# AQS.net
KiCad netlist of a schematic drawn in EAGLE
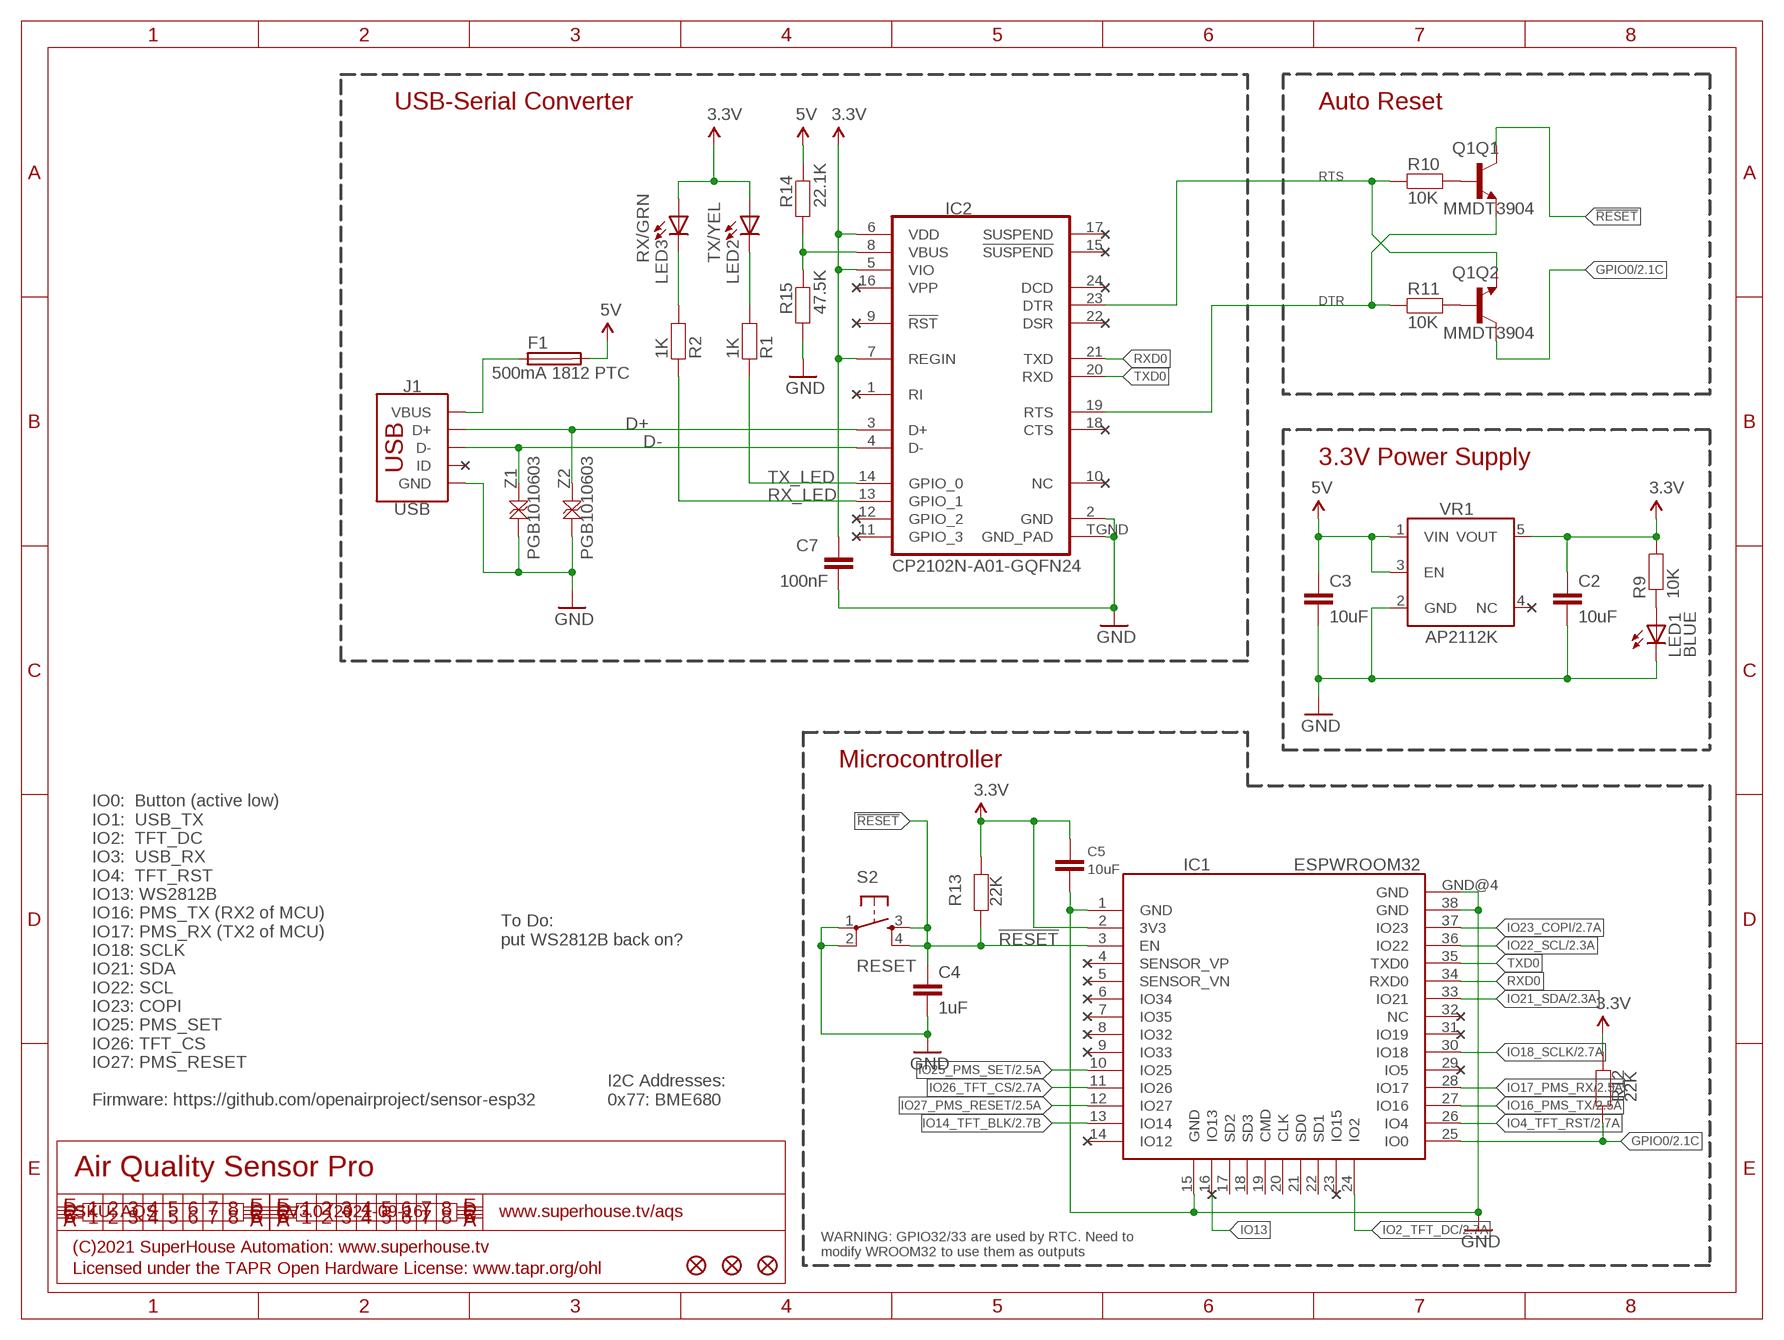
[diagram p0: schematic, sheet 1]
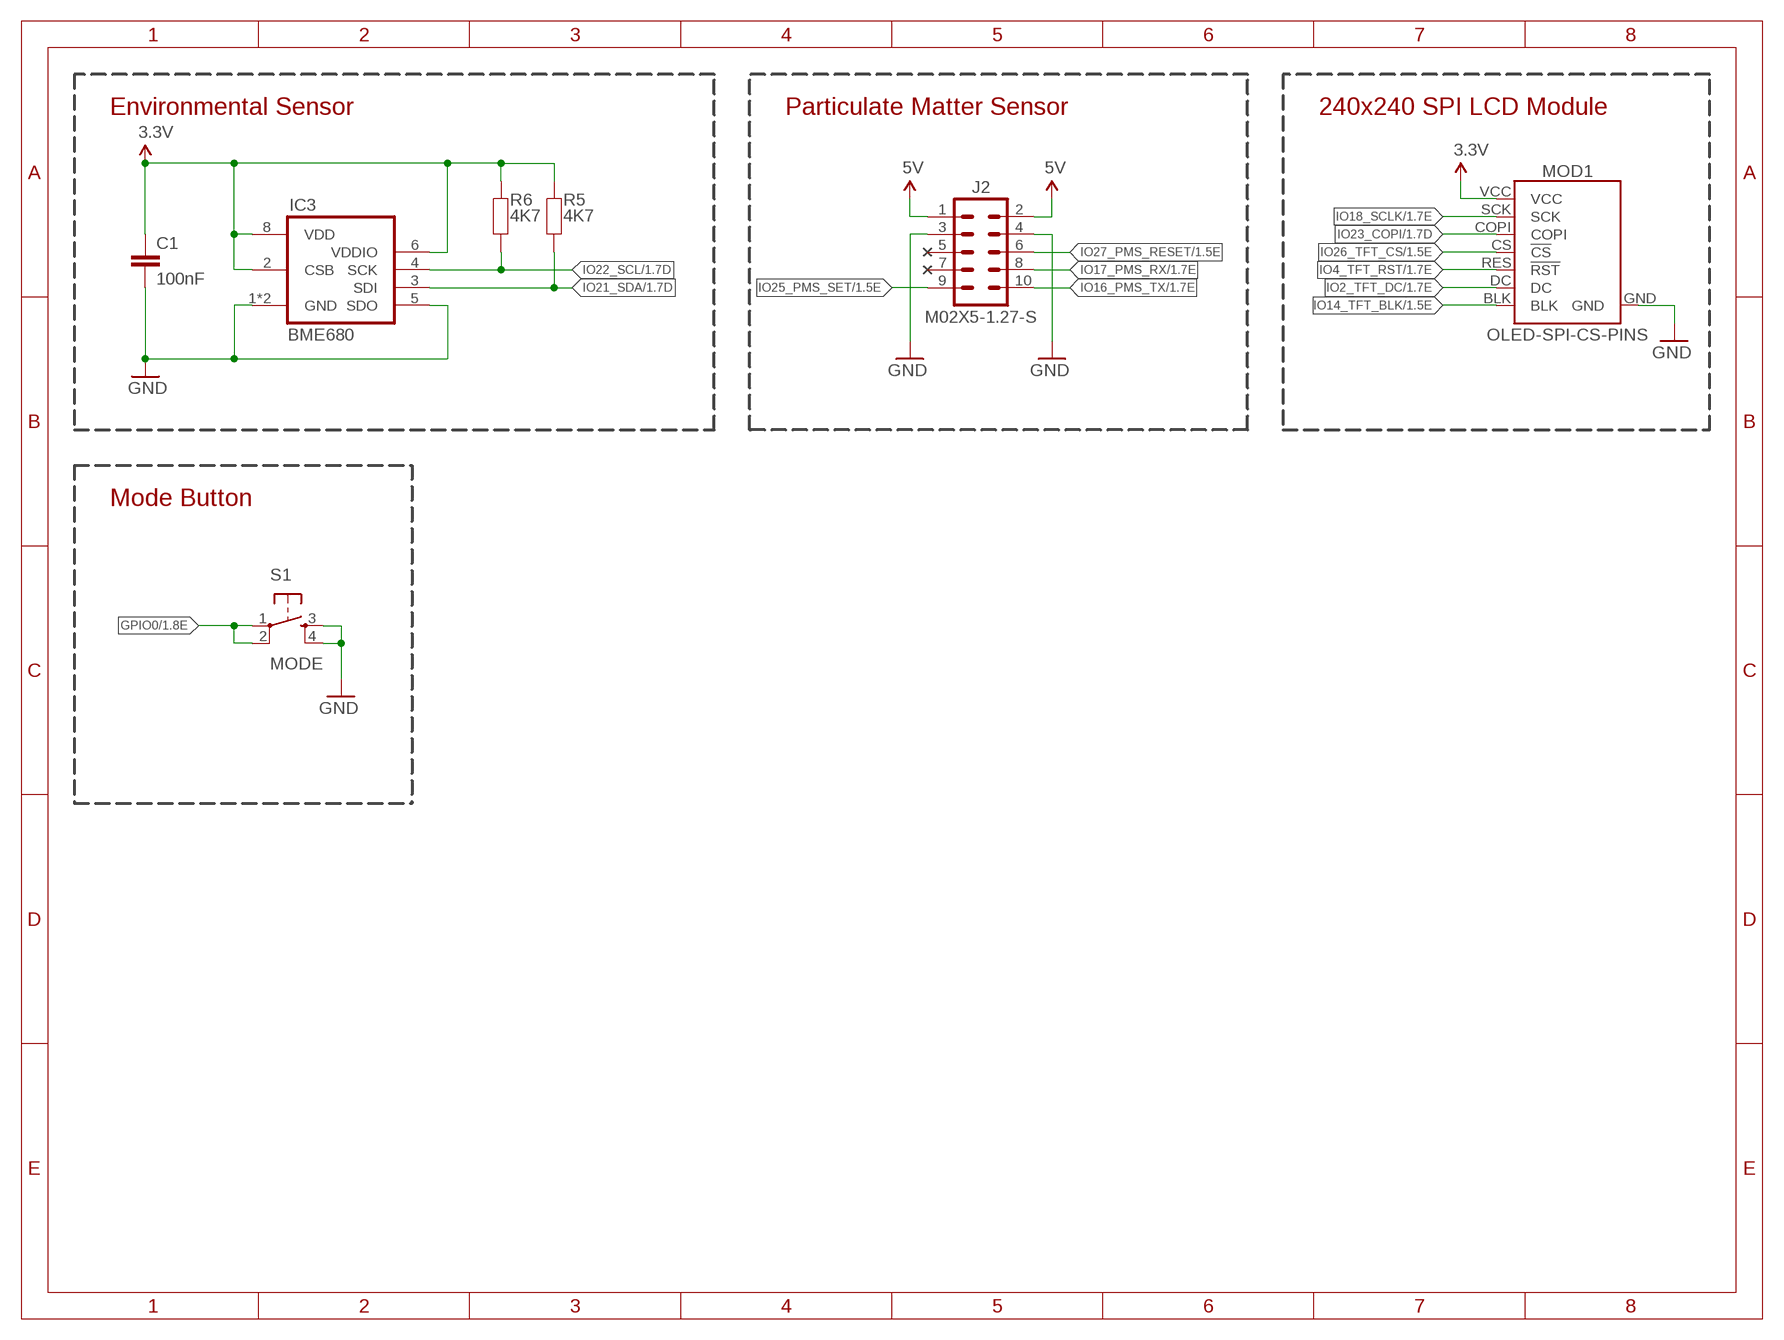
[diagram p1: schematic, sheet 2]

(export (version "E")
  (design (tool "Eeschema 10.0.6"))
  (components
    (comp (ref "C1")
      (value "100nF")
      (footprint "eagle-import:C0603")
      (libsource (lib "eagle-import") (part "CAP0603"))
    )
    (comp (ref "IC3")
      (value "BME680")
      (footprint "eagle-import:BME680")
      (libsource (lib "eagle-import") (part "BME680"))
    )
    (comp (ref "J2")
      (value "M02X5-1.27-S")
      (footprint "eagle-import:2X05-1.27-S")
      (libsource (lib "eagle-import") (part "M02X5-1.27-S"))
    )
    (comp (ref "MOD1")
      (value "OLED-SPI-CS-PINS")
      (footprint "eagle-import:OLED-240X240-1.54")
      (libsource (lib "eagle-import") (part "OLED-SPI-CS-PINS"))
    )
    (comp (ref "R5")
      (value "4K7")
      (footprint "eagle-import:R0603")
      (libsource (lib "eagle-import") (part "RESISTOR0603"))
    )
    (comp (ref "R6")
      (value "4K7")
      (footprint "eagle-import:R0603")
      (libsource (lib "eagle-import") (part "RESISTOR0603"))
    )
    (comp (ref "S1")
      (value "MODE")
      (footprint "eagle-import:TACTILE-PTH-4.5MM")
      (libsource (lib "eagle-import") (part "TAC_SWITCH-PTH-4.5"))
    )
    (comp (ref "C2")
      (value "10uF")
      (footprint "eagle-import:C0805")
      (libsource (lib "eagle-import") (part "CAP0805"))
    )
    (comp (ref "C3")
      (value "10uF")
      (footprint "eagle-import:C0805")
      (libsource (lib "eagle-import") (part "CAP0805"))
    )
    (comp (ref "C4")
      (value "1uF")
      (footprint "eagle-import:C0603")
      (libsource (lib "eagle-import") (part "CAP0603"))
    )
    (comp (ref "C5")
      (value "10uF")
      (footprint "eagle-import:C0805")
      (libsource (lib "eagle-import") (part "CAP0805"))
    )
    (comp (ref "C7")
      (value "100nF")
      (footprint "eagle-import:C0603")
      (libsource (lib "eagle-import") (part "CAP0603"))
    )
    (comp (ref "F1")
      (value "500mA 1812 PTC")
      (footprint "eagle-import:1206")
      (libsource (lib "eagle-import") (part "PTC-1206"))
    )
    (comp (ref "IC1")
      (value "ESPWROOM32")
      (footprint "eagle-import:ESPWROOM32")
      (libsource (lib "eagle-import") (part "ESPWROOM32"))
    )
    (comp (ref "IC2")
      (value "CP2102N-A01-GQFN24")
      (footprint "eagle-import:QFN-24")
      (libsource (lib "eagle-import") (part "CP2104"))
    )
    (comp (ref "J1")
      (value "USB")
      (footprint "eagle-import:USB-MICROB-VERT")
      (libsource (lib "eagle-import") (part "USB-B-5P-VERT"))
    )
    (comp (ref "LED1")
      (value "BLUE")
      (footprint "eagle-import:LED-0603")
      (libsource (lib "eagle-import") (part "LED0603"))
    )
    (comp (ref "LED2")
      (value "TX/YEL")
      (footprint "eagle-import:LED-0603")
      (libsource (lib "eagle-import") (part "LED0603"))
    )
    (comp (ref "LED3")
      (value "RX/GRN")
      (footprint "eagle-import:LED-0603")
      (libsource (lib "eagle-import") (part "LED0603"))
    )
    (comp (ref "Q1")
      (value "MMDT3904")
      (footprint "eagle-import:SOT-363")
      (libsource (lib "eagle-import") (part "TRANS_NPN_DUAL-MMDT3904"))
    )
    (comp (ref "R1")
      (value "1K")
      (footprint "eagle-import:R0603")
      (libsource (lib "eagle-import") (part "RESISTOR0603"))
    )
    (comp (ref "R2")
      (value "1K")
      (footprint "eagle-import:R0603")
      (libsource (lib "eagle-import") (part "RESISTOR0603"))
    )
    (comp (ref "R9")
      (value "10K")
      (footprint "eagle-import:R0603")
      (libsource (lib "eagle-import") (part "RESISTOR0603"))
    )
    (comp (ref "R10")
      (value "10K")
      (footprint "eagle-import:R0603")
      (libsource (lib "eagle-import") (part "RESISTOR0603"))
    )
    (comp (ref "R11")
      (value "10K")
      (footprint "eagle-import:R0603")
      (libsource (lib "eagle-import") (part "RESISTOR0603"))
    )
    (comp (ref "R12")
      (value "22K")
      (footprint "eagle-import:R0603")
      (libsource (lib "eagle-import") (part "RESISTOR0603"))
    )
    (comp (ref "R13")
      (value "22K")
      (footprint "eagle-import:R0603")
      (libsource (lib "eagle-import") (part "RESISTOR0603"))
    )
    (comp (ref "R14")
      (value "22.1K")
      (footprint "eagle-import:R0603")
      (libsource (lib "eagle-import") (part "RESISTOR0603"))
    )
    (comp (ref "R15")
      (value "47.5K")
      (footprint "eagle-import:R0603")
      (libsource (lib "eagle-import") (part "RESISTOR0603"))
    )
    (comp (ref "S2")
      (value "RESET")
      (footprint "eagle-import:TACTILE-PTH-4.5MM")
      (libsource (lib "eagle-import") (part "TAC_SWITCH-PTH-4.5"))
    )
    (comp (ref "U$23")
      (value "FIDUCIAL1X2")
      (footprint "eagle-import:FIDUCIAL-1X2")
      (libsource (lib "eagle-import") (part "FIDUCIAL1X2"))
    )
    (comp (ref "U$24")
      (value "FIDUCIAL1X2")
      (footprint "eagle-import:FIDUCIAL-1X2")
      (libsource (lib "eagle-import") (part "FIDUCIAL1X2"))
    )
    (comp (ref "U$25")
      (value "FIDUCIAL1X2")
      (footprint "eagle-import:FIDUCIAL-1X2")
      (libsource (lib "eagle-import") (part "FIDUCIAL1X2"))
    )
    (comp (ref "VR1")
      (value "AP2112KSOT25")
      (footprint "eagle-import:SOT23-5")
      (libsource (lib "eagle-import") (part "AP2112KSOT25"))
    )
    (comp (ref "Z1")
      (value "PGB1010603")
      (footprint "eagle-import:TVS0603")
      (libsource (lib "eagle-import") (part "TVS0603"))
    )
    (comp (ref "Z2")
      (value "PGB1010603")
      (footprint "eagle-import:TVS0603")
      (libsource (lib "eagle-import") (part "TVS0603"))
    )
  )
  (nets
    (net (code "1") (name "3.3V") (class "Default")
      (node (ref "C1") (pin "1") (pinfunction "1_1") (pintype "passive"))
      (node (ref "C2") (pin "1") (pinfunction "1_1") (pintype "passive"))
      (node (ref "C5") (pin "1") (pinfunction "1_1") (pintype "passive"))
      (node (ref "C7") (pin "1") (pinfunction "1_1") (pintype "passive"))
      (node (ref "IC1") (pin "2") (pinfunction "3V3_2") (pintype "power_in"))
      (node (ref "IC2") (pin "5") (pinfunction "VIO_5") (pintype "bidirectional"))
      (node (ref "IC2") (pin "6") (pinfunction "VDD_6") (pintype "power_in"))
      (node (ref "IC2") (pin "7") (pinfunction "REGIN_7") (pintype "power_in"))
      (node (ref "IC3") (pin "2") (pinfunction "CSB_2") (pintype "input"))
      (node (ref "IC3") (pin "6") (pinfunction "VDDIO_6") (pintype "power_in"))
      (node (ref "IC3") (pin "8") (pinfunction "VDD_8") (pintype "power_in"))
      (node (ref "LED2") (pin "A") (pinfunction "A_A") (pintype "passive"))
      (node (ref "LED3") (pin "A") (pinfunction "A_A") (pintype "passive"))
      (node (ref "MOD1") (pin "VCC") (pinfunction "VCC_VCC") (pintype "bidirectional"))
      (node (ref "R12") (pin "1") (pinfunction "1_1") (pintype "passive"))
      (node (ref "R13") (pin "1") (pinfunction "1_1") (pintype "passive"))
      (node (ref "R5") (pin "2") (pinfunction "2_2") (pintype "passive"))
      (node (ref "R6") (pin "2") (pinfunction "2_2") (pintype "passive"))
      (node (ref "R9") (pin "2") (pinfunction "2_2") (pintype "passive"))
      (node (ref "VR1") (pin "5") (pinfunction "VOUT_5") (pintype "bidirectional"))
    )
    (net (code "2") (name "5V") (class "Default")
      (node (ref "C3") (pin "1") (pinfunction "1_1") (pintype "passive"))
      (node (ref "F1") (pin "2") (pinfunction "2_2") (pintype "passive"))
      (node (ref "J2") (pin "1") (pinfunction "1_1") (pintype "passive"))
      (node (ref "J2") (pin "2") (pinfunction "2_2") (pintype "passive"))
      (node (ref "R14") (pin "2") (pinfunction "2_2") (pintype "passive"))
      (node (ref "VR1") (pin "1") (pinfunction "VIN_1") (pintype "bidirectional"))
      (node (ref "VR1") (pin "3") (pinfunction "EN_3") (pintype "bidirectional"))
    )
    (net (code "3") (name "D+") (class "Default")
      (node (ref "IC2") (pin "3") (pinfunction "D+_3") (pintype "bidirectional"))
      (node (ref "J1") (pin "3") (pinfunction "D+_3") (pintype "bidirectional"))
      (node (ref "Z2") (pin "2") (pinfunction "2_2") (pintype "passive"))
    )
    (net (code "4") (name "D-") (class "Default")
      (node (ref "IC2") (pin "4") (pinfunction "D-_4") (pintype "bidirectional"))
      (node (ref "J1") (pin "2") (pinfunction "D-_2") (pintype "bidirectional"))
      (node (ref "Z1") (pin "2") (pinfunction "2_2") (pintype "passive"))
    )
    (net (code "5") (name "DTR") (class "Default")
      (node (ref "IC2") (pin "23") (pinfunction "DTR_23") (pintype "output"))
      (node (ref "Q1") (pin "1") (pinfunction "E_1") (pintype "passive"))
      (node (ref "R10") (pin "1") (pinfunction "1_1") (pintype "passive"))
    )
    (net (code "6") (name "GND") (class "Default")
      (node (ref "C1") (pin "2") (pinfunction "2_2") (pintype "passive"))
      (node (ref "C2") (pin "2") (pinfunction "2_2") (pintype "passive"))
      (node (ref "C3") (pin "2") (pinfunction "2_2") (pintype "passive"))
      (node (ref "C4") (pin "2") (pinfunction "2_2") (pintype "passive"))
      (node (ref "C5") (pin "2") (pinfunction "2_2") (pintype "passive"))
      (node (ref "C7") (pin "2") (pinfunction "2_2") (pintype "passive"))
      (node (ref "IC1") (pin "1") (pinfunction "GND_1") (pintype "power_in"))
      (node (ref "IC1") (pin "15") (pinfunction "GND_15") (pintype "power_in"))
      (node (ref "IC1") (pin "38") (pinfunction "GND_38") (pintype "power_in"))
      (node (ref "IC1") (pin "GND@4") (pinfunction "GND_GND@4") (pintype "power_in"))
      (node (ref "IC2") (pin "2") (pinfunction "GND_2") (pintype "power_in"))
      (node (ref "IC2") (pin "TGND") (pinfunction "GND_PAD_TGND") (pintype "power_in"))
      (node (ref "IC3") (pin "1") (pinfunction "GND_1") (pintype "power_in"))
      (node (ref "IC3") (pin "5") (pinfunction "SDO_5") (pintype "input"))
      (node (ref "IC3") (pin "7") (pinfunction "GND_7") (pintype "power_in"))
      (node (ref "J1") (pin "5") (pinfunction "GND_5") (pintype "power_in"))
      (node (ref "J1") (pin "POST1") (pinfunction "GND_POST1") (pintype "power_in"))
      (node (ref "J1") (pin "POST2") (pinfunction "GND_POST2") (pintype "power_in"))
      (node (ref "J2") (pin "3") (pinfunction "3_3") (pintype "passive"))
      (node (ref "J2") (pin "4") (pinfunction "4_4") (pintype "passive"))
      (node (ref "LED1") (pin "C") (pinfunction "C_C") (pintype "passive"))
      (node (ref "MOD1") (pin "GND") (pinfunction "GND_GND") (pintype "bidirectional"))
      (node (ref "R15") (pin "1") (pinfunction "1_1") (pintype "passive"))
      (node (ref "S1") (pin "3") (pinfunction "3_3") (pintype "passive"))
      (node (ref "S1") (pin "4") (pinfunction "4_4") (pintype "passive"))
      (node (ref "S2") (pin "1") (pinfunction "1_1") (pintype "passive"))
      (node (ref "S2") (pin "2") (pinfunction "2_2") (pintype "passive"))
      (node (ref "VR1") (pin "2") (pinfunction "GND_2") (pintype "bidirectional"))
      (node (ref "Z1") (pin "1") (pinfunction "1_1") (pintype "passive"))
      (node (ref "Z2") (pin "1") (pinfunction "1_1") (pintype "passive"))
    )
    (net (code "7") (name "GPIO0") (class "Default")
      (node (ref "IC1") (pin "25") (pinfunction "IO0_25") (pintype "bidirectional"))
      (node (ref "Q1") (pin "6") (pinfunction "C_6") (pintype "passive"))
      (node (ref "R12") (pin "2") (pinfunction "2_2") (pintype "passive"))
      (node (ref "S1") (pin "1") (pinfunction "1_1") (pintype "passive"))
      (node (ref "S1") (pin "2") (pinfunction "2_2") (pintype "passive"))
    )
    (net (code "8") (name "IO2_TFT_DC") (class "Default")
      (node (ref "IC1") (pin "24") (pinfunction "IO2_24") (pintype "bidirectional"))
      (node (ref "MOD1") (pin "DC") (pinfunction "DC_DC") (pintype "bidirectional"))
    )
    (net (code "9") (name "IO4_TFT_RST") (class "Default")
      (node (ref "IC1") (pin "26") (pinfunction "IO4_26") (pintype "bidirectional"))
      (node (ref "MOD1") (pin "RES") (pinfunction "~{RST}_RES") (pintype "bidirectional"))
    )
    (net (code "10") (name "IO13") (class "Default")
      (node (ref "IC1") (pin "16") (pinfunction "IO13_16") (pintype "bidirectional"))
    )
    (net (code "11") (name "IO14_TFT_BLK") (class "Default")
      (node (ref "IC1") (pin "13") (pinfunction "IO14_13") (pintype "bidirectional"))
      (node (ref "MOD1") (pin "BLK") (pinfunction "BLK_BLK") (pintype "bidirectional"))
    )
    (net (code "12") (name "IO16_PMS_TX") (class "Default")
      (node (ref "IC1") (pin "27") (pinfunction "IO16_27") (pintype "bidirectional"))
      (node (ref "J2") (pin "10") (pinfunction "10_10") (pintype "passive"))
    )
    (net (code "13") (name "IO17_PMS_RX") (class "Default")
      (node (ref "IC1") (pin "28") (pinfunction "IO17_28") (pintype "bidirectional"))
      (node (ref "J2") (pin "8") (pinfunction "8_8") (pintype "passive"))
    )
    (net (code "14") (name "IO18_SCLK") (class "Default")
      (node (ref "IC1") (pin "30") (pinfunction "IO18_30") (pintype "bidirectional"))
      (node (ref "MOD1") (pin "SCK") (pinfunction "SCK_SCK") (pintype "bidirectional"))
    )
    (net (code "15") (name "IO21_SDA") (class "Default")
      (node (ref "IC1") (pin "33") (pinfunction "IO21_33") (pintype "bidirectional"))
      (node (ref "IC3") (pin "3") (pinfunction "SDI_3") (pintype "bidirectional"))
      (node (ref "R5") (pin "1") (pinfunction "1_1") (pintype "passive"))
    )
    (net (code "16") (name "IO22_SCL") (class "Default")
      (node (ref "IC1") (pin "36") (pinfunction "IO22_36") (pintype "bidirectional"))
      (node (ref "IC3") (pin "4") (pinfunction "SCK_4") (pintype "bidirectional"))
      (node (ref "R6") (pin "1") (pinfunction "1_1") (pintype "passive"))
    )
    (net (code "17") (name "IO23_COPI") (class "Default")
      (node (ref "IC1") (pin "37") (pinfunction "IO23_37") (pintype "bidirectional"))
      (node (ref "MOD1") (pin "COPI") (pinfunction "COPI_COPI") (pintype "bidirectional"))
    )
    (net (code "18") (name "IO25_PMS_SET") (class "Default")
      (node (ref "IC1") (pin "10") (pinfunction "IO25_10") (pintype "bidirectional"))
      (node (ref "J2") (pin "9") (pinfunction "9_9") (pintype "passive"))
    )
    (net (code "19") (name "IO26_TFT_CS") (class "Default")
      (node (ref "IC1") (pin "11") (pinfunction "IO26_11") (pintype "bidirectional"))
      (node (ref "MOD1") (pin "CS") (pinfunction "~{CS}_CS") (pintype "bidirectional"))
    )
    (net (code "20") (name "IO27_PMS_RESET") (class "Default")
      (node (ref "IC1") (pin "12") (pinfunction "IO27_12") (pintype "bidirectional"))
      (node (ref "J2") (pin "6") (pinfunction "6_6") (pintype "passive"))
    )
    (net (code "21") (name "Net-(IC2-VBUS)") (class "Default")
      (node (ref "IC2") (pin "8") (pinfunction "VBUS_8") (pintype "bidirectional"))
      (node (ref "R14") (pin "1") (pinfunction "1_1") (pintype "passive"))
      (node (ref "R15") (pin "2") (pinfunction "2_2") (pintype "passive"))
    )
    (net (code "22") (name "Net-(J1-VBUS)") (class "Default")
      (node (ref "F1") (pin "1") (pinfunction "1_1") (pintype "passive"))
      (node (ref "J1") (pin "1") (pinfunction "VBUS_1") (pintype "power_in"))
    )
    (net (code "23") (name "Net-(LED1-PadA)") (class "Default")
      (node (ref "LED1") (pin "A") (pinfunction "A_A") (pintype "passive"))
      (node (ref "R9") (pin "1") (pinfunction "1_1") (pintype "passive"))
    )
    (net (code "24") (name "Net-(LED2-PadC)") (class "Default")
      (node (ref "LED2") (pin "C") (pinfunction "C_C") (pintype "passive"))
      (node (ref "R1") (pin "2") (pinfunction "2_2") (pintype "passive"))
    )
    (net (code "25") (name "Net-(LED3-PadC)") (class "Default")
      (node (ref "LED3") (pin "C") (pinfunction "C_C") (pintype "passive"))
      (node (ref "R2") (pin "2") (pinfunction "2_2") (pintype "passive"))
    )
    (net (code "26") (name "Net-(Q1A-B)") (class "Default")
      (node (ref "Q1") (pin "5") (pinfunction "B_5") (pintype "passive"))
      (node (ref "R10") (pin "2") (pinfunction "2_2") (pintype "passive"))
    )
    (net (code "27") (name "Net-(Q1B-B)") (class "Default")
      (node (ref "Q1") (pin "2") (pinfunction "B_2") (pintype "passive"))
      (node (ref "R11") (pin "2") (pinfunction "2_2") (pintype "passive"))
    )
    (net (code "28") (name "RTS") (class "Default")
      (node (ref "IC2") (pin "19") (pinfunction "RTS_19") (pintype "output"))
      (node (ref "Q1") (pin "4") (pinfunction "E_4") (pintype "passive"))
      (node (ref "R11") (pin "1") (pinfunction "1_1") (pintype "passive"))
    )
    (net (code "29") (name "RXD0") (class "Default")
      (node (ref "IC1") (pin "34") (pinfunction "RXD0_34") (pintype "bidirectional"))
      (node (ref "IC2") (pin "21") (pinfunction "TXD_21") (pintype "output"))
    )
    (net (code "30") (name "RX_LED") (class "Default")
      (node (ref "IC2") (pin "13") (pinfunction "GPIO_1_13") (pintype "bidirectional"))
      (node (ref "R2") (pin "1") (pinfunction "1_1") (pintype "passive"))
    )
    (net (code "31") (name "TXD0") (class "Default")
      (node (ref "IC1") (pin "35") (pinfunction "TXD0_35") (pintype "bidirectional"))
      (node (ref "IC2") (pin "20") (pinfunction "RXD_20") (pintype "input"))
    )
    (net (code "32") (name "TX_LED") (class "Default")
      (node (ref "IC2") (pin "14") (pinfunction "GPIO_0_14") (pintype "bidirectional"))
      (node (ref "R1") (pin "1") (pinfunction "1_1") (pintype "passive"))
    )
    (net (code "33") (name "unconnected-(IC1-CLK-Pad20)") (class "Default")
      (node (ref "IC1") (pin "20") (pinfunction "CLK_20") (pintype "bidirectional"))
    )
    (net (code "34") (name "unconnected-(IC1-CMD-Pad19)") (class "Default")
      (node (ref "IC1") (pin "19") (pinfunction "CMD_19") (pintype "bidirectional"))
    )
    (net (code "35") (name "unconnected-(IC1-IO5-Pad29)") (class "Default")
      (node (ref "IC1") (pin "29") (pinfunction "IO5_29") (pintype "bidirectional"))
    )
    (net (code "36") (name "unconnected-(IC1-IO12-Pad14)") (class "Default")
      (node (ref "IC1") (pin "14") (pinfunction "IO12_14") (pintype "bidirectional"))
    )
    (net (code "37") (name "unconnected-(IC1-IO15-Pad23)") (class "Default")
      (node (ref "IC1") (pin "23") (pinfunction "IO15_23") (pintype "bidirectional"))
    )
    (net (code "38") (name "unconnected-(IC1-IO19-Pad31)") (class "Default")
      (node (ref "IC1") (pin "31") (pinfunction "IO19_31") (pintype "bidirectional"))
    )
    (net (code "39") (name "unconnected-(IC1-IO32-Pad8)") (class "Default")
      (node (ref "IC1") (pin "8") (pinfunction "IO32_8") (pintype "bidirectional"))
    )
    (net (code "40") (name "unconnected-(IC1-IO33-Pad9)") (class "Default")
      (node (ref "IC1") (pin "9") (pinfunction "IO33_9") (pintype "bidirectional"))
    )
    (net (code "41") (name "unconnected-(IC1-IO34-Pad6)") (class "Default")
      (node (ref "IC1") (pin "6") (pinfunction "IO34_6") (pintype "bidirectional"))
    )
    (net (code "42") (name "unconnected-(IC1-IO35-Pad7)") (class "Default")
      (node (ref "IC1") (pin "7") (pinfunction "IO35_7") (pintype "bidirectional"))
    )
    (net (code "43") (name "unconnected-(IC1-NC-Pad32)") (class "Default")
      (node (ref "IC1") (pin "32") (pinfunction "NC_32") (pintype "bidirectional"))
    )
    (net (code "44") (name "unconnected-(IC1-SD0-Pad21)") (class "Default")
      (node (ref "IC1") (pin "21") (pinfunction "SD0_21") (pintype "bidirectional"))
    )
    (net (code "45") (name "unconnected-(IC1-SD1-Pad22)") (class "Default")
      (node (ref "IC1") (pin "22") (pinfunction "SD1_22") (pintype "bidirectional"))
    )
    (net (code "46") (name "unconnected-(IC1-SD2-Pad17)") (class "Default")
      (node (ref "IC1") (pin "17") (pinfunction "SD2_17") (pintype "bidirectional"))
    )
    (net (code "47") (name "unconnected-(IC1-SD3-Pad18)") (class "Default")
      (node (ref "IC1") (pin "18") (pinfunction "SD3_18") (pintype "bidirectional"))
    )
    (net (code "48") (name "unconnected-(IC1-SENSOR_VN-Pad5)") (class "Default")
      (node (ref "IC1") (pin "5") (pinfunction "SENSOR_VN_5") (pintype "bidirectional"))
    )
    (net (code "49") (name "unconnected-(IC1-SENSOR_VP-Pad4)") (class "Default")
      (node (ref "IC1") (pin "4") (pinfunction "SENSOR_VP_4") (pintype "bidirectional"))
    )
    (net (code "50") (name "unconnected-(IC2-CTS-Pad18)") (class "Default")
      (node (ref "IC2") (pin "18") (pinfunction "CTS_18") (pintype "input"))
    )
    (net (code "51") (name "unconnected-(IC2-DCD-Pad24)") (class "Default")
      (node (ref "IC2") (pin "24") (pinfunction "DCD_24") (pintype "input"))
    )
    (net (code "52") (name "unconnected-(IC2-DSR-Pad22)") (class "Default")
      (node (ref "IC2") (pin "22") (pinfunction "DSR_22") (pintype "input"))
    )
    (net (code "53") (name "unconnected-(IC2-GPIO_2-Pad12)") (class "Default")
      (node (ref "IC2") (pin "12") (pinfunction "GPIO_2_12") (pintype "bidirectional"))
    )
    (net (code "54") (name "unconnected-(IC2-GPIO_3-Pad11)") (class "Default")
      (node (ref "IC2") (pin "11") (pinfunction "GPIO_3_11") (pintype "bidirectional"))
    )
    (net (code "55") (name "unconnected-(IC2-NC-Pad10)") (class "Default")
      (node (ref "IC2") (pin "10") (pinfunction "NC_10") (pintype "input"))
    )
    (net (code "56") (name "unconnected-(IC2-RI-Pad1)") (class "Default")
      (node (ref "IC2") (pin "1") (pinfunction "RI_1") (pintype "input"))
    )
    (net (code "57") (name "unconnected-(IC2-SUSPEND-Pad17)") (class "Default")
      (node (ref "IC2") (pin "17") (pinfunction "SUSPEND_17") (pintype "output"))
    )
    (net (code "58") (name "unconnected-(IC2-VPP-Pad16)") (class "Default")
      (node (ref "IC2") (pin "16") (pinfunction "VPP_16") (pintype "bidirectional"))
    )
    (net (code "59") (name "unconnected-(IC2-~{RST}-Pad9)") (class "Default")
      (node (ref "IC2") (pin "9") (pinfunction "~{RST}_9") (pintype "bidirectional"))
    )
    (net (code "60") (name "unconnected-(IC2-~{SUSPEND}-Pad15)") (class "Default")
      (node (ref "IC2") (pin "15") (pinfunction "~{SUSPEND}_15") (pintype "output"))
    )
    (net (code "61") (name "unconnected-(J1-ID-Pad4)") (class "Default")
      (node (ref "J1") (pin "4") (pinfunction "ID_4") (pintype "bidirectional"))
    )
    (net (code "62") (name "unconnected-(J2-Pad5)") (class "Default")
      (node (ref "J2") (pin "5") (pinfunction "5_5") (pintype "passive"))
    )
    (net (code "63") (name "unconnected-(J2-Pad7)") (class "Default")
      (node (ref "J2") (pin "7") (pinfunction "7_7") (pintype "passive"))
    )
    (net (code "64") (name "unconnected-(VR1-NC-Pad4)") (class "Default")
      (node (ref "VR1") (pin "4") (pinfunction "NC_4") (pintype "bidirectional"))
    )
    (net (code "65") (name "~{RESET}") (class "Default")
      (node (ref "C4") (pin "1") (pinfunction "1_1") (pintype "passive"))
      (node (ref "IC1") (pin "3") (pinfunction "EN_3") (pintype "bidirectional"))
      (node (ref "Q1") (pin "3") (pinfunction "C_3") (pintype "passive"))
      (node (ref "R13") (pin "2") (pinfunction "2_2") (pintype "passive"))
      (node (ref "S2") (pin "3") (pinfunction "3_3") (pintype "passive"))
      (node (ref "S2") (pin "4") (pinfunction "4_4") (pintype "passive"))
    )
  )
)
